# GBE2_PHY.net
KiCad netlist of a schematic drawn in Altium Designer
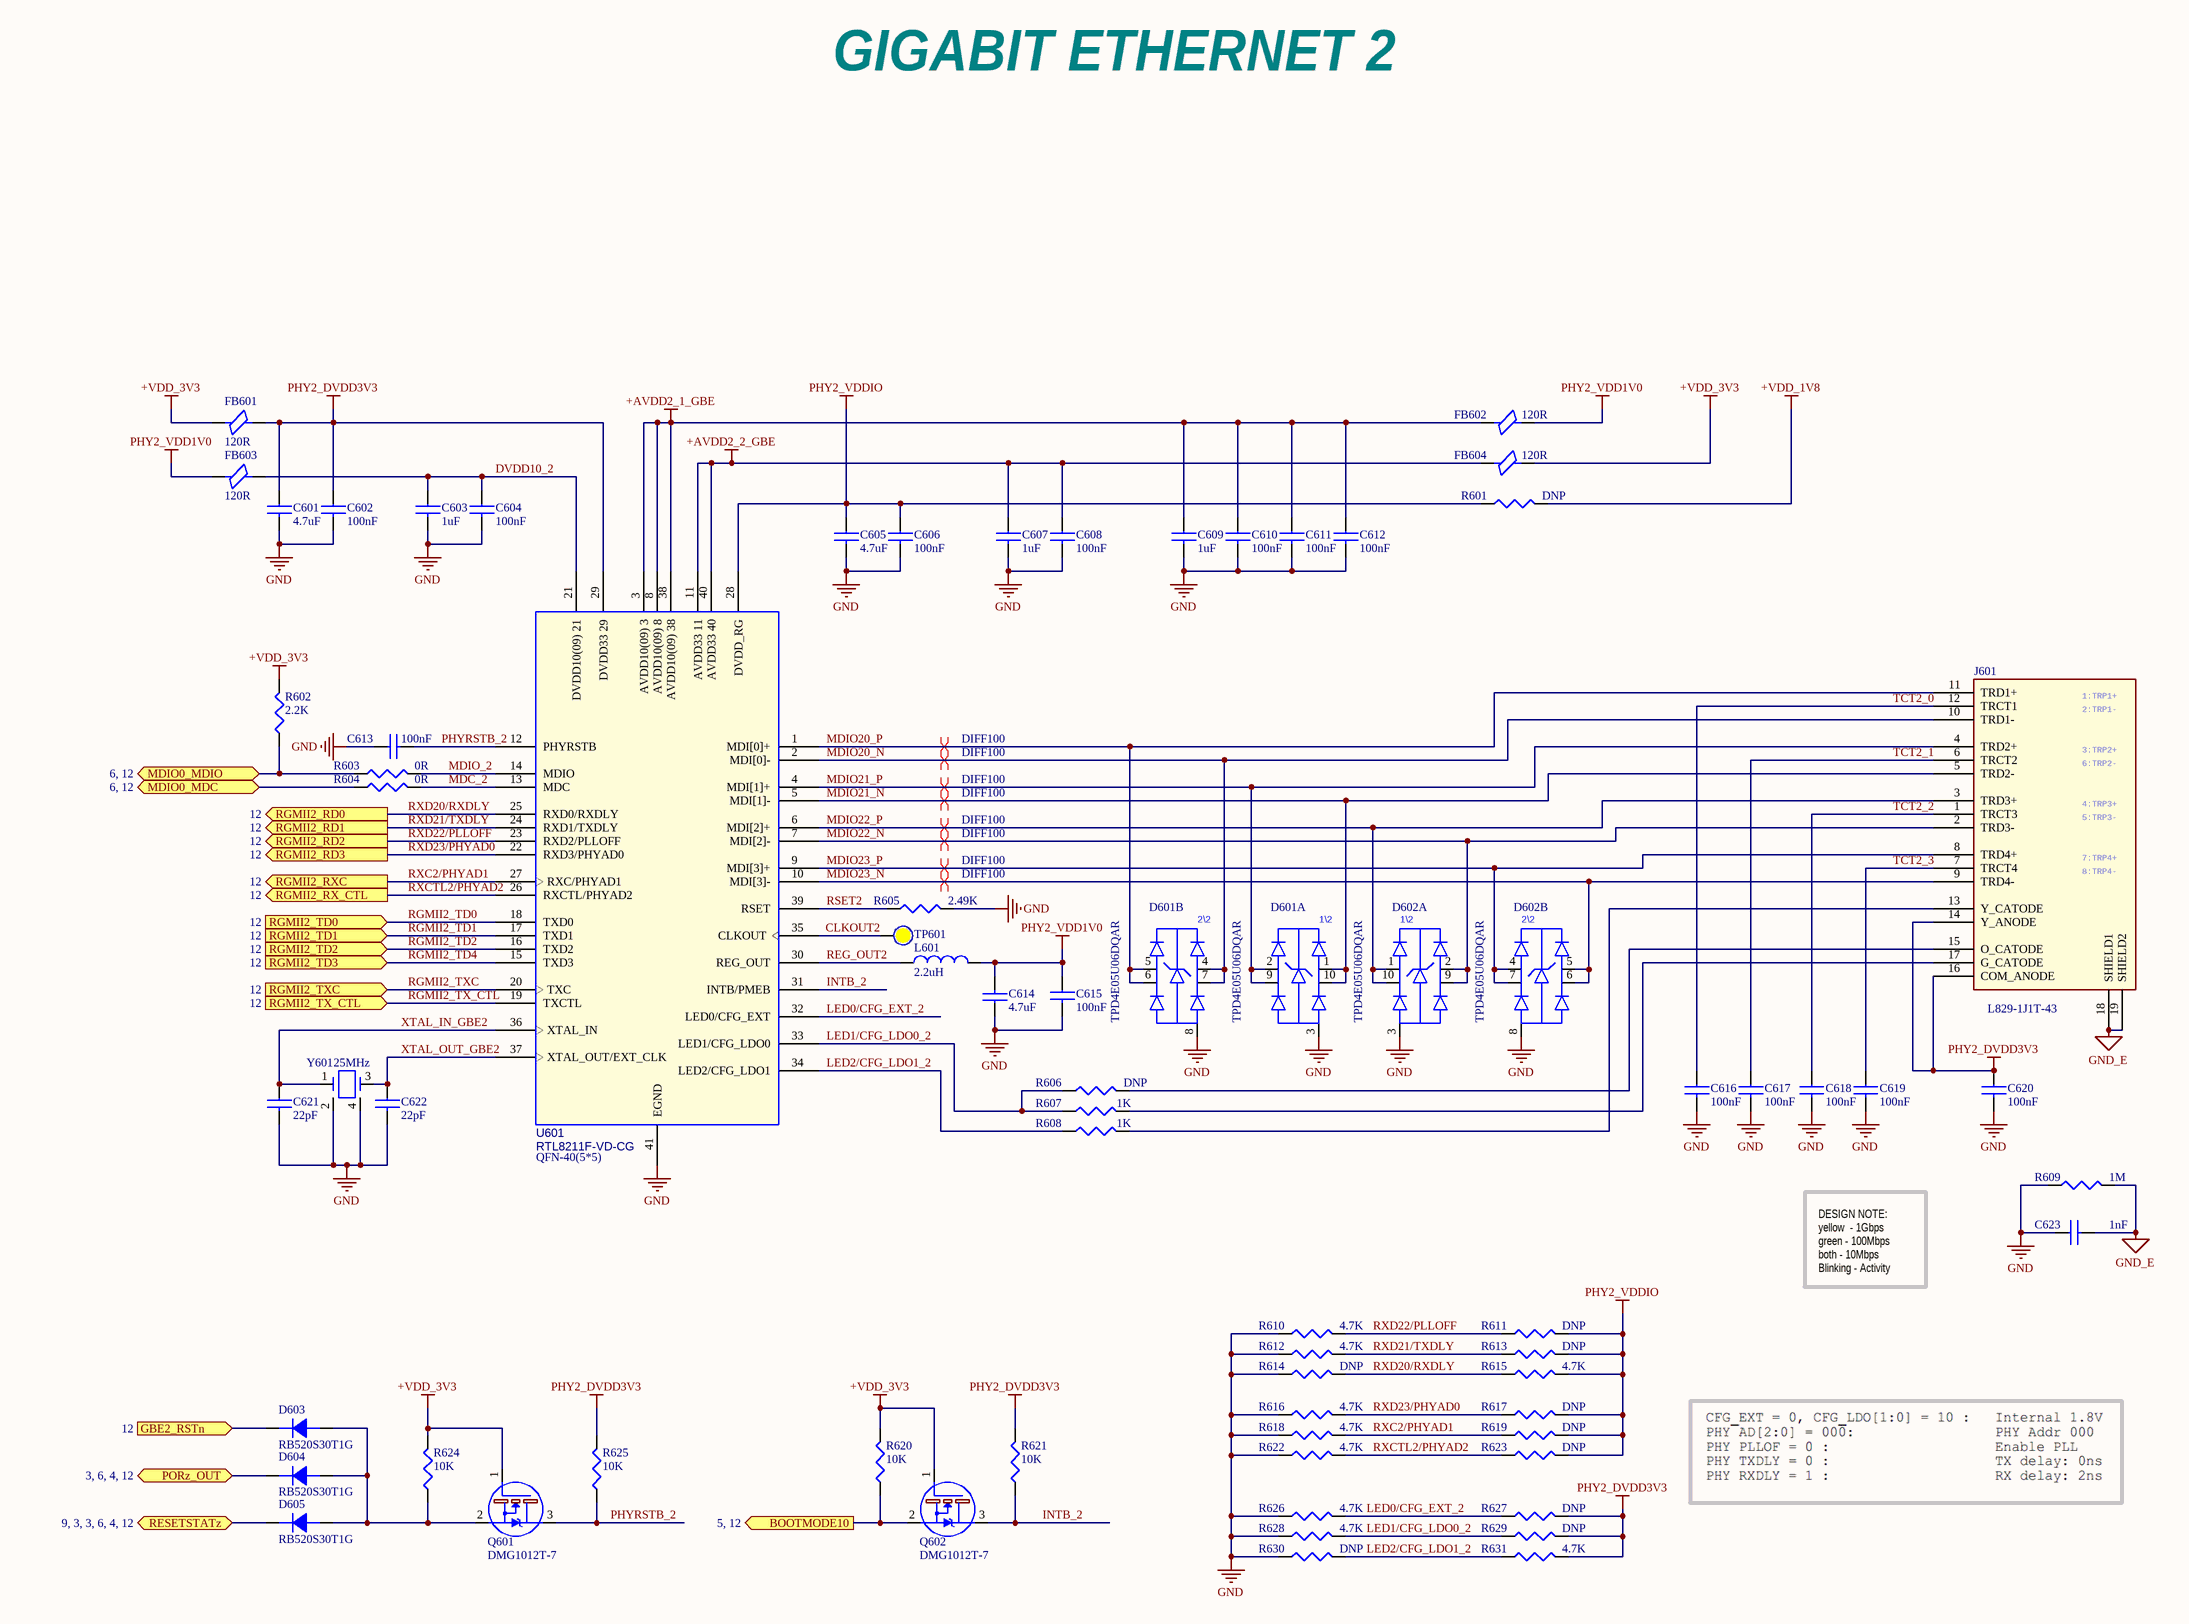
[diagram p0: GBE2 PHY.SchDoc]

(export (version "E")
  (design (tool "Eeschema 10.0.6"))
  (components
    (comp (ref "C601")
      (value "4.7uF")
      (footprint "C0402")
      (description "Multilayer Ceramic Capacitor, 4.7 uF, 6.3V, ± 10%, X5R, 0402 [1005 Metric]")
      (fields
        (field (name "MANUFACTURER") "Yageo")
        (field (name "MANUFACTURER PART NUMBER") "CC0402MRX5R5BB475")
      )
      (libsource (lib "Schlib SOM AM625") (part "CC0402MRX5R5BB475"))
    )
    (comp (ref "C602")
      (value "100nF")
      (footprint "C0201")
      (description "Multilayer Ceramic Capacitor, 0.1 uF, 16 V, ± 10%, X5R, 0201 [0603 Metric]")
      (fields
        (field (name "MANUFACTURER") "Yageo")
        (field (name "MANUFACTURER PART NUMBER") "CC0201KRX5R6BB104")
      )
      (libsource (lib "Schlib SOM AM625") (part "CC0201KRX5R6BB104"))
    )
    (comp (ref "C603")
      (value "1uF")
      (footprint "C0201")
      (description "1 µF ±20% 6.3V Ceramic Capacitor X5R 0201 (0603 Metric)")
      (fields
        (field (name "MANUFACTURER") "Yageo")
        (field (name "MANUFACTURER PART NUMBER") "CC0201MRX5R5BB105")
      )
      (libsource (lib "Schlib SOM AM625") (part "CC0201MRX5R5BB105"))
    )
    (comp (ref "C604")
      (value "100nF")
      (footprint "C0201")
      (description "Multilayer Ceramic Capacitor, 0.1 uF, 16 V, ± 10%, X5R, 0201 [0603 Metric]")
      (fields
        (field (name "MANUFACTURER") "Yageo")
        (field (name "MANUFACTURER PART NUMBER") "CC0201KRX5R6BB104")
      )
      (libsource (lib "Schlib SOM AM625") (part "CC0201KRX5R6BB104"))
    )
    (comp (ref "C605")
      (value "4.7uF")
      (footprint "C0402")
      (description "Multilayer Ceramic Capacitor, 4.7 uF, 6.3V, ± 10%, X5R, 0402 [1005 Metric]")
      (fields
        (field (name "MANUFACTURER") "Yageo")
        (field (name "MANUFACTURER PART NUMBER") "CC0402MRX5R5BB475")
      )
      (libsource (lib "Schlib SOM AM625") (part "CC0402MRX5R5BB475"))
    )
    (comp (ref "C606")
      (value "100nF")
      (footprint "C0201")
      (description "Multilayer Ceramic Capacitor, 0.1 uF, 16 V, ± 10%, X5R, 0201 [0603 Metric]")
      (fields
        (field (name "MANUFACTURER") "Yageo")
        (field (name "MANUFACTURER PART NUMBER") "CC0201KRX5R6BB104")
      )
      (libsource (lib "Schlib SOM AM625") (part "CC0201KRX5R6BB104"))
    )
    (comp (ref "C607")
      (value "1uF")
      (footprint "C0201")
      (description "1 µF ±20% 6.3V Ceramic Capacitor X5R 0201 (0603 Metric)")
      (fields
        (field (name "MANUFACTURER") "Yageo")
        (field (name "MANUFACTURER PART NUMBER") "CC0201MRX5R5BB105")
      )
      (libsource (lib "Schlib SOM AM625") (part "CC0201MRX5R5BB105"))
    )
    (comp (ref "C608")
      (value "100nF")
      (footprint "C0201")
      (description "Multilayer Ceramic Capacitor, 0.1 uF, 16 V, ± 10%, X5R, 0201 [0603 Metric]")
      (fields
        (field (name "MANUFACTURER") "Yageo")
        (field (name "MANUFACTURER PART NUMBER") "CC0201KRX5R6BB104")
      )
      (libsource (lib "Schlib SOM AM625") (part "CC0201KRX5R6BB104"))
    )
    (comp (ref "C609")
      (value "1uF")
      (footprint "C0201")
      (description "1 µF ±20% 6.3V Ceramic Capacitor X5R 0201 (0603 Metric)")
      (fields
        (field (name "MANUFACTURER") "Yageo")
        (field (name "MANUFACTURER PART NUMBER") "CC0201MRX5R5BB105")
      )
      (libsource (lib "Schlib SOM AM625") (part "CC0201MRX5R5BB105"))
    )
    (comp (ref "C610")
      (value "100nF")
      (footprint "C0201")
      (description "Multilayer Ceramic Capacitor, 0.1 uF, 16 V, ± 10%, X5R, 0201 [0603 Metric]")
      (fields
        (field (name "MANUFACTURER") "Yageo")
        (field (name "MANUFACTURER PART NUMBER") "CC0201KRX5R6BB104")
      )
      (libsource (lib "Schlib SOM AM625") (part "CC0201KRX5R6BB104"))
    )
    (comp (ref "C611")
      (value "100nF")
      (footprint "C0201")
      (description "Multilayer Ceramic Capacitor, 0.1 uF, 16 V, ± 10%, X5R, 0201 [0603 Metric]")
      (fields
        (field (name "MANUFACTURER") "Yageo")
        (field (name "MANUFACTURER PART NUMBER") "CC0201KRX5R6BB104")
      )
      (libsource (lib "Schlib SOM AM625") (part "CC0201KRX5R6BB104"))
    )
    (comp (ref "C612")
      (value "100nF")
      (footprint "C0201")
      (description "Multilayer Ceramic Capacitor, 0.1 uF, 16 V, ± 10%, X5R, 0201 [0603 Metric]")
      (fields
        (field (name "MANUFACTURER") "Yageo")
        (field (name "MANUFACTURER PART NUMBER") "CC0201KRX5R6BB104")
      )
      (libsource (lib "Schlib SOM AM625") (part "CC0201KRX5R6BB104"))
    )
    (comp (ref "C613")
      (value "100nF")
      (footprint "C0201")
      (description "Multilayer Ceramic Capacitor, 0.1 uF, 16 V, ± 10%, X5R, 0201 [0603 Metric]")
      (fields
        (field (name "MANUFACTURER") "Yageo")
        (field (name "MANUFACTURER PART NUMBER") "CC0201KRX5R6BB104")
      )
      (libsource (lib "Schlib SOM AM625") (part "CC0201KRX5R6BB104"))
    )
    (comp (ref "C614")
      (value "4.7uF")
      (footprint "C0402")
      (description "Multilayer Ceramic Capacitor, 4.7 uF, 6.3V, ± 10%, X5R, 0402 [1005 Metric]")
      (fields
        (field (name "MANUFACTURER") "Yageo")
        (field (name "MANUFACTURER PART NUMBER") "CC0402MRX5R5BB475")
      )
      (libsource (lib "Schlib SOM AM625") (part "CC0402MRX5R5BB475"))
    )
    (comp (ref "C615")
      (value "100nF")
      (footprint "C0201")
      (description "Multilayer Ceramic Capacitor, 0.1 uF, 16 V, ± 10%, X5R, 0201 [0603 Metric]")
      (fields
        (field (name "MANUFACTURER") "Yageo")
        (field (name "MANUFACTURER PART NUMBER") "CC0201KRX5R6BB104")
      )
      (libsource (lib "Schlib SOM AM625") (part "CC0201KRX5R6BB104"))
    )
    (comp (ref "C616")
      (value "100nF")
      (footprint "C0402")
      (description "Multilayer Ceramic Capacitor, 0.1 uF, 50 V, ± 10%, X5R, 0402 [1005 Metric]")
      (fields
        (field (name "MANUFACTURER") "TDK")
        (field (name "MANUFACTURER PART NUMBER") "C1005X5R1H104K050BB")
      )
      (libsource (lib "Schlib SOM AM625") (part "C1005X5R1H104K050BB"))
    )
    (comp (ref "C617")
      (value "100nF")
      (footprint "C0402")
      (description "Multilayer Ceramic Capacitor, 0.1 uF, 50 V, ± 10%, X5R, 0402 [1005 Metric]")
      (fields
        (field (name "MANUFACTURER") "TDK")
        (field (name "MANUFACTURER PART NUMBER") "C1005X5R1H104K050BB")
      )
      (libsource (lib "Schlib SOM AM625") (part "C1005X5R1H104K050BB"))
    )
    (comp (ref "C618")
      (value "100nF")
      (footprint "C0402")
      (description "Multilayer Ceramic Capacitor, 0.1 uF, 50 V, ± 10%, X5R, 0402 [1005 Metric]")
      (fields
        (field (name "MANUFACTURER") "TDK")
        (field (name "MANUFACTURER PART NUMBER") "C1005X5R1H104K050BB")
      )
      (libsource (lib "Schlib SOM AM625") (part "C1005X5R1H104K050BB"))
    )
    (comp (ref "C619")
      (value "100nF")
      (footprint "C0402")
      (description "Multilayer Ceramic Capacitor, 0.1 uF, 50 V, ± 10%, X5R, 0402 [1005 Metric]")
      (fields
        (field (name "MANUFACTURER") "TDK")
        (field (name "MANUFACTURER PART NUMBER") "C1005X5R1H104K050BB")
      )
      (libsource (lib "Schlib SOM AM625") (part "C1005X5R1H104K050BB"))
    )
    (comp (ref "C620")
      (value "100nF")
      (footprint "C0402")
      (description "Multilayer Ceramic Capacitor, 0.1 uF, 50 V, ± 10%, X5R, 0402 [1005 Metric]")
      (fields
        (field (name "MANUFACTURER") "TDK")
        (field (name "MANUFACTURER PART NUMBER") "C1005X5R1H104K050BB")
      )
      (libsource (lib "Schlib SOM AM625") (part "C1005X5R1H104K050BB"))
    )
    (comp (ref "C621")
      (value "22pF")
      (footprint "C0201")
      (description "0201 22 pF 50 V ±5 % Tolerance NP0 SMT Multilayer Ceramic Capacitor")
      (fields
        (field (name "MANUFACTURER") "Yageo")
        (field (name "MANUFACTURER PART NUMBER") "CC0201JRNPO9BN220")
      )
      (libsource (lib "Schlib SOM AM625") (part "CC0201JRNPO9BN220"))
    )
    (comp (ref "C622")
      (value "22pF")
      (footprint "C0201")
      (description "0201 22 pF 50 V ±5 % Tolerance NP0 SMT Multilayer Ceramic Capacitor")
      (fields
        (field (name "MANUFACTURER") "Yageo")
        (field (name "MANUFACTURER PART NUMBER") "CC0201JRNPO9BN220")
      )
      (libsource (lib "Schlib SOM AM625") (part "CC0201JRNPO9BN220"))
    )
    (comp (ref "C623")
      (value "1nF")
      (footprint "C1206B/3216MM")
      (description "Cap Ceramic 0.001uF 1000V X7R 10% Pad SMD 1206 125°C Low ESR Automotive Medical T/R")
      (fields
        (field (name "MANUFACTURER") "KEMET")
        (field (name "MANUFACTURER PART NUMBER") "C1206C102KDRACAUTO")
      )
      (libsource (lib "Schlib SOM AM625") (part "C1206C102KDRACAUTO"))
    )
    (comp (ref "D601")
      (value "TPD4E05U06DQAR")
      (footprint "10-USON")
      (description "Quad 0.5-pF, 5.5-V, ±12-kV ESD protection diode for USB, HDMI & High Speed Interfaces")
      (fields (field (name "MANUFACTURER") "Texas Instruments"))
      (libsource (lib "Schlib SOM AM625") (part "TPD4E05U06DQAR"))
    )
    (comp (ref "D602")
      (value "TPD4E05U06DQAR")
      (footprint "10-USON")
      (description "Quad 0.5-pF, 5.5-V, ±12-kV ESD protection diode for USB, HDMI & High Speed Interfaces")
      (fields (field (name "MANUFACTURER") "Texas Instruments"))
      (libsource (lib "Schlib SOM AM625") (part "TPD4E05U06DQAR"))
    )
    (comp (ref "D603")
      (value "RB520S30T1G")
      (footprint "sod_523")
      (description "Diode Schottky 30V 0.2A 2-Pin SOD-523 T/R - Product that comes on tape, but is not reeled")
      (fields (field (name "MANUFACTURER") "ON Semiconductor"))
      (libsource (lib "Schlib SOM AM625") (part "RB520S30T1G"))
    )
    (comp (ref "D604")
      (value "RB520S30T1G")
      (footprint "sod_523")
      (description "Diode Schottky 30V 0.2A 2-Pin SOD-523 T/R - Product that comes on tape, but is not reeled")
      (fields (field (name "MANUFACTURER") "ON Semiconductor"))
      (libsource (lib "Schlib SOM AM625") (part "RB520S30T1G"))
    )
    (comp (ref "D605")
      (value "RB520S30T1G")
      (footprint "sod_523")
      (description "Diode Schottky 30V 0.2A 2-Pin SOD-523 T/R - Product that comes on tape, but is not reeled")
      (fields (field (name "MANUFACTURER") "ON Semiconductor"))
      (libsource (lib "Schlib SOM AM625") (part "RB520S30T1G"))
    )
    (comp (ref "FB601")
      (value "120R")
      (footprint "FB0402")
      (description "Ferrite Beads Multi-Layer 120Ohm 25% 100MHz 1.3A 0.09Ohm DCR 0402 Automotive T/R")
      (fields
        (field (name "MANUFACTURER") "Murata")
        (field (name "MANUFACTURER PART NUMBER") "BLM15PD121SZ1D")
      )
      (libsource (lib "Schlib SOM AM625") (part "BLM15PD121SZ1D"))
    )
    (comp (ref "FB602")
      (value "120R")
      (footprint "FB0402")
      (description "Ferrite Beads Multi-Layer 120Ohm 25% 100MHz 1.3A 0.09Ohm DCR 0402 Automotive T/R")
      (fields
        (field (name "MANUFACTURER") "Murata")
        (field (name "MANUFACTURER PART NUMBER") "BLM15PD121SZ1D")
      )
      (libsource (lib "Schlib SOM AM625") (part "BLM15PD121SZ1D"))
    )
    (comp (ref "FB603")
      (value "120R")
      (footprint "FB0402")
      (description "Ferrite Beads Multi-Layer 120Ohm 25% 100MHz 1.3A 0.09Ohm DCR 0402 Automotive T/R")
      (fields
        (field (name "MANUFACTURER") "Murata")
        (field (name "MANUFACTURER PART NUMBER") "BLM15PD121SZ1D")
      )
      (libsource (lib "Schlib SOM AM625") (part "BLM15PD121SZ1D"))
    )
    (comp (ref "FB604")
      (value "120R")
      (footprint "FB0402")
      (description "Ferrite Beads Multi-Layer 120Ohm 25% 100MHz 1.3A 0.09Ohm DCR 0402 Automotive T/R")
      (fields
        (field (name "MANUFACTURER") "Murata")
        (field (name "MANUFACTURER PART NUMBER") "BLM15PD121SZ1D")
      )
      (libsource (lib "Schlib SOM AM625") (part "BLM15PD121SZ1D"))
    )
    (comp (ref "J601")
      (value "L829-1J1T-43")
      (footprint "L829-1J1T-43")
      (description "CONN MAGJACK 1PORT SHLD 1000BT")
      (fields
        (field (name "MANUFACTURER") "Bel Fuse Inc")
        (field (name ".CHECKED PCB") "RF")
        (field (name ".CHECKED SCH") "RF")
      )
      (libsource (lib "Schlib SOM AM625") (part "L829-1J1T-43"))
    )
    (comp (ref "L601")
      (value "2.2uH")
      (footprint "l2016")
      (description "Inductor Power Shielded Wirewound 2.2uH 20% 1MHz Metal 1.4A 0.168Ohm DCR 0806 T/R")
      (fields
        (field (name "MANUFACTURER") "Murata")
        (field (name "MANUFACTURER PART NUMBER") "DFE201610P-2R2M=P2")
      )
      (libsource (lib "Schlib SOM AM625") (part "DFE201610P-2R2M=P2"))
    )
    (comp (ref "Q601")
      (value "DMG1012T-7")
      (footprint "sot_523")
      (description "Transistor MOSFET NTR4003NT1G, SOT23, ON Semi")
      (fields (field (name "MANUFACTURER") "Diodes"))
      (libsource (lib "Schlib SOM AM625") (part "DMG1012T-7"))
    )
    (comp (ref "Q602")
      (value "DMG1012T-7")
      (footprint "sot_523")
      (description "Transistor MOSFET NTR4003NT1G, SOT23, ON Semi")
      (fields (field (name "MANUFACTURER") "Diodes"))
      (libsource (lib "Schlib SOM AM625") (part "DMG1012T-7"))
    )
    (comp (ref "R601")
      (value "DNP")
      (footprint "R0402")
      (description "Zero Ohm Resistor, Jumper, 0402 [1005 Metric], Thick Film, 63 mW, 1 A, Surface Mount")
      (fields
        (field (name "MANUFACTURER") "Yageo")
        (field (name "MANUFACTURER PART NUMBER") "RC0402JR-070RL")
      )
      (libsource (lib "Schlib SOM AM625") (part "RC0402JR-070RL"))
    )
    (comp (ref "R602")
      (value "2.2K")
      (footprint "R0201")
      (description "SMD Chip Resistor, 2.2 kOhm, ± 1%, 50 mW, 0201 [0603 Metric], Thick Film, General Purpose")
      (fields
        (field (name "MANUFACTURER") "Yageo")
        (field (name "MANUFACTURER PART NUMBER") "RC0201FR-072K2L")
      )
      (libsource (lib "Schlib SOM AM625") (part "RC0201FR-072K2L"))
    )
    (comp (ref "R603")
      (value "0R")
      (footprint "R0201")
      (description "Zero Ohm Resistor, Jumper, 0201 [0603 Metric], Thick Film, 50 mW, 500 mA, Surface Mount")
      (fields
        (field (name "MANUFACTURER") "Yageo")
        (field (name "MANUFACTURER PART NUMBER") "RC0201JR-070RL")
      )
      (libsource (lib "Schlib SOM AM625") (part "RC0201JR-070RL"))
    )
    (comp (ref "R604")
      (value "0R")
      (footprint "R0201")
      (description "Zero Ohm Resistor, Jumper, 0201 [0603 Metric], Thick Film, 50 mW, 500 mA, Surface Mount")
      (fields
        (field (name "MANUFACTURER") "Yageo")
        (field (name "MANUFACTURER PART NUMBER") "RC0201JR-070RL")
      )
      (libsource (lib "Schlib SOM AM625") (part "RC0201JR-070RL"))
    )
    (comp (ref "R605")
      (value "2.49K")
      (footprint "R0201")
      (description "SMD Chip Resistor, 2.49 kOhm, ± 1%, 50 mW, 0201 [0603 Metric], Thick Film, General Purpose")
      (fields
        (field (name "MANUFACTURER") "Yageo")
        (field (name "MANUFACTURER PART NUMBER") "RC0201FR-072K49L")
      )
      (libsource (lib "Schlib SOM AM625") (part "RC0201FR-072K49L"))
    )
    (comp (ref "R606")
      (value "DNP")
      (footprint "R0402")
      (description "Zero Ohm Resistor, Jumper, 0402 [1005 Metric], Thick Film, 63 mW, 1 A, Surface Mount")
      (fields
        (field (name "MANUFACTURER") "Yageo")
        (field (name "MANUFACTURER PART NUMBER") "RC0402JR-070RL")
      )
      (libsource (lib "Schlib SOM AM625") (part "RC0402JR-070RL"))
    )
    (comp (ref "R607")
      (value "1K")
      (footprint "R0402")
      (description "SMD Chip Resistor, 1 kOhm, ± 1%, 63 mW, 0402 [1005 Metric], Thick Film, General Purpose")
      (fields
        (field (name "MANUFACTURER") "Yageo")
        (field (name "MANUFACTURER PART NUMBER") "RC0402FR-071KL")
      )
      (libsource (lib "Schlib SOM AM625") (part "RC0402FR-071KL"))
    )
    (comp (ref "R608")
      (value "1K")
      (footprint "R0402")
      (description "SMD Chip Resistor, 1 kOhm, ± 1%, 63 mW, 0402 [1005 Metric], Thick Film, General Purpose")
      (fields
        (field (name "MANUFACTURER") "Yageo")
        (field (name "MANUFACTURER PART NUMBER") "RC0402FR-071KL")
      )
      (libsource (lib "Schlib SOM AM625") (part "RC0402FR-071KL"))
    )
    (comp (ref "R609")
      (value "1M")
      (footprint "R1206B/3216MM")
      (description "SMD Chip Resistor, 1 MOhm, ± 1%, 250 mW, 1206 [3216 Metric], Thick Film, General Purpose")
      (fields
        (field (name "MANUFACTURER") "Yageo")
        (field (name "MANUFACTURER PART NUMBER") "RC1206FR-071ML")
      )
      (libsource (lib "Schlib SOM AM625") (part "RC1206FR-071ML"))
    )
    (comp (ref "R610")
      (value "4.7K")
      (footprint "R0201")
      (description "SMD Chip Resistor, 4.7 kOhm, ± 5%, 50 mW, 0201 [0603 Metric], Thick Film, General Purpose")
      (fields
        (field (name "MANUFACTURER") "Yageo")
        (field (name "MANUFACTURER PART NUMBER") "RC0201JR-074K7L")
      )
      (libsource (lib "Schlib SOM AM625") (part "RC0201JR-074K7L"))
    )
    (comp (ref "R611")
      (value "DNP")
      (footprint "R0201")
      (description "SMD Chip Resistor, 4.7 kOhm, ± 5%, 50 mW, 0201 [0603 Metric], Thick Film, General Purpose")
      (fields
        (field (name "MANUFACTURER") "Yageo")
        (field (name "MANUFACTURER PART NUMBER") "RC0201JR-074K7L")
      )
      (libsource (lib "Schlib SOM AM625") (part "RC0201JR-074K7L"))
    )
    (comp (ref "R612")
      (value "4.7K")
      (footprint "R0201")
      (description "SMD Chip Resistor, 4.7 kOhm, ± 5%, 50 mW, 0201 [0603 Metric], Thick Film, General Purpose")
      (fields
        (field (name "MANUFACTURER") "Yageo")
        (field (name "MANUFACTURER PART NUMBER") "RC0201JR-074K7L")
      )
      (libsource (lib "Schlib SOM AM625") (part "RC0201JR-074K7L"))
    )
    (comp (ref "R613")
      (value "DNP")
      (footprint "R0201")
      (description "SMD Chip Resistor, 4.7 kOhm, ± 5%, 50 mW, 0201 [0603 Metric], Thick Film, General Purpose")
      (fields
        (field (name "MANUFACTURER") "Yageo")
        (field (name "MANUFACTURER PART NUMBER") "RC0201JR-074K7L")
      )
      (libsource (lib "Schlib SOM AM625") (part "RC0201JR-074K7L"))
    )
    (comp (ref "R614")
      (value "DNP")
      (footprint "R0201")
      (description "SMD Chip Resistor, 4.7 kOhm, ± 5%, 50 mW, 0201 [0603 Metric], Thick Film, General Purpose")
      (fields
        (field (name "MANUFACTURER") "Yageo")
        (field (name "MANUFACTURER PART NUMBER") "RC0201JR-074K7L")
      )
      (libsource (lib "Schlib SOM AM625") (part "RC0201JR-074K7L"))
    )
    (comp (ref "R615")
      (value "4.7K")
      (footprint "R0201")
      (description "SMD Chip Resistor, 4.7 kOhm, ± 5%, 50 mW, 0201 [0603 Metric], Thick Film, General Purpose")
      (fields
        (field (name "MANUFACTURER") "Yageo")
        (field (name "MANUFACTURER PART NUMBER") "RC0201JR-074K7L")
      )
      (libsource (lib "Schlib SOM AM625") (part "RC0201JR-074K7L"))
    )
    (comp (ref "R616")
      (value "4.7K")
      (footprint "R0201")
      (description "SMD Chip Resistor, 4.7 kOhm, ± 5%, 50 mW, 0201 [0603 Metric], Thick Film, General Purpose")
      (fields
        (field (name "MANUFACTURER") "Yageo")
        (field (name "MANUFACTURER PART NUMBER") "RC0201JR-074K7L")
      )
      (libsource (lib "Schlib SOM AM625") (part "RC0201JR-074K7L"))
    )
    (comp (ref "R617")
      (value "DNP")
      (footprint "R0201")
      (description "SMD Chip Resistor, 4.7 kOhm, ± 5%, 50 mW, 0201 [0603 Metric], Thick Film, General Purpose")
      (fields
        (field (name "MANUFACTURER") "Yageo")
        (field (name "MANUFACTURER PART NUMBER") "RC0201JR-074K7L")
      )
      (libsource (lib "Schlib SOM AM625") (part "RC0201JR-074K7L"))
    )
    (comp (ref "R618")
      (value "4.7K")
      (footprint "R0201")
      (description "SMD Chip Resistor, 4.7 kOhm, ± 5%, 50 mW, 0201 [0603 Metric], Thick Film, General Purpose")
      (fields
        (field (name "MANUFACTURER") "Yageo")
        (field (name "MANUFACTURER PART NUMBER") "RC0201JR-074K7L")
      )
      (libsource (lib "Schlib SOM AM625") (part "RC0201JR-074K7L"))
    )
    (comp (ref "R619")
      (value "DNP")
      (footprint "R0201")
      (description "SMD Chip Resistor, 4.7 kOhm, ± 5%, 50 mW, 0201 [0603 Metric], Thick Film, General Purpose")
      (fields
        (field (name "MANUFACTURER") "Yageo")
        (field (name "MANUFACTURER PART NUMBER") "RC0201JR-074K7L")
      )
      (libsource (lib "Schlib SOM AM625") (part "RC0201JR-074K7L"))
    )
    (comp (ref "R620")
      (value "10K")
      (footprint "R0201")
      (description "SMD Chip Resistor, 10 kOhm, ± 1%, 50 mW, 0201 [0603 Metric], Thick Film, General Purpose")
      (fields
        (field (name "MANUFACTURER") "Yageo")
        (field (name "MANUFACTURER PART NUMBER") "RC0201FR-0710KL")
      )
      (libsource (lib "Schlib SOM AM625") (part "RC0201FR-0710KL"))
    )
    (comp (ref "R621")
      (value "10K")
      (footprint "R0201")
      (description "SMD Chip Resistor, 10 kOhm, ± 1%, 50 mW, 0201 [0603 Metric], Thick Film, General Purpose")
      (fields
        (field (name "MANUFACTURER") "Yageo")
        (field (name "MANUFACTURER PART NUMBER") "RC0201FR-0710KL")
      )
      (libsource (lib "Schlib SOM AM625") (part "RC0201FR-0710KL"))
    )
    (comp (ref "R622")
      (value "4.7K")
      (footprint "R0201")
      (description "SMD Chip Resistor, 4.7 kOhm, ± 5%, 50 mW, 0201 [0603 Metric], Thick Film, General Purpose")
      (fields
        (field (name "MANUFACTURER") "Yageo")
        (field (name "MANUFACTURER PART NUMBER") "RC0201JR-074K7L")
      )
      (libsource (lib "Schlib SOM AM625") (part "RC0201JR-074K7L"))
    )
    (comp (ref "R623")
      (value "DNP")
      (footprint "R0201")
      (description "SMD Chip Resistor, 4.7 kOhm, ± 5%, 50 mW, 0201 [0603 Metric], Thick Film, General Purpose")
      (fields
        (field (name "MANUFACTURER") "Yageo")
        (field (name "MANUFACTURER PART NUMBER") "RC0201JR-074K7L")
      )
      (libsource (lib "Schlib SOM AM625") (part "RC0201JR-074K7L"))
    )
    (comp (ref "R624")
      (value "10K")
      (footprint "R0201")
      (description "SMD Chip Resistor, 10 kOhm, ± 1%, 50 mW, 0201 [0603 Metric], Thick Film, General Purpose")
      (fields
        (field (name "MANUFACTURER") "Yageo")
        (field (name "MANUFACTURER PART NUMBER") "RC0201FR-0710KL")
      )
      (libsource (lib "Schlib SOM AM625") (part "RC0201FR-0710KL"))
    )
    (comp (ref "R625")
      (value "10K")
      (footprint "R0201")
      (description "SMD Chip Resistor, 10 kOhm, ± 1%, 50 mW, 0201 [0603 Metric], Thick Film, General Purpose")
      (fields
        (field (name "MANUFACTURER") "Yageo")
        (field (name "MANUFACTURER PART NUMBER") "RC0201FR-0710KL")
      )
      (libsource (lib "Schlib SOM AM625") (part "RC0201FR-0710KL"))
    )
    (comp (ref "R626")
      (value "4.7K")
      (footprint "R0201")
      (description "SMD Chip Resistor, 4.7 kOhm, ± 5%, 50 mW, 0201 [0603 Metric], Thick Film, General Purpose")
      (fields
        (field (name "MANUFACTURER") "Yageo")
        (field (name "MANUFACTURER PART NUMBER") "RC0201JR-074K7L")
      )
      (libsource (lib "Schlib SOM AM625") (part "RC0201JR-074K7L"))
    )
    (comp (ref "R627")
      (value "DNP")
      (footprint "R0201")
      (description "SMD Chip Resistor, 4.7 kOhm, ± 5%, 50 mW, 0201 [0603 Metric], Thick Film, General Purpose")
      (fields
        (field (name "MANUFACTURER") "Yageo")
        (field (name "MANUFACTURER PART NUMBER") "RC0201JR-074K7L")
      )
      (libsource (lib "Schlib SOM AM625") (part "RC0201JR-074K7L"))
    )
    (comp (ref "R628")
      (value "4.7K")
      (footprint "R0201")
      (description "SMD Chip Resistor, 4.7 kOhm, ± 5%, 50 mW, 0201 [0603 Metric], Thick Film, General Purpose")
      (fields
        (field (name "MANUFACTURER") "Yageo")
        (field (name "MANUFACTURER PART NUMBER") "RC0201JR-074K7L")
      )
      (libsource (lib "Schlib SOM AM625") (part "RC0201JR-074K7L"))
    )
    (comp (ref "R629")
      (value "DNP")
      (footprint "R0201")
      (description "SMD Chip Resistor, 4.7 kOhm, ± 5%, 50 mW, 0201 [0603 Metric], Thick Film, General Purpose")
      (fields
        (field (name "MANUFACTURER") "Yageo")
        (field (name "MANUFACTURER PART NUMBER") "RC0201JR-074K7L")
      )
      (libsource (lib "Schlib SOM AM625") (part "RC0201JR-074K7L"))
    )
    (comp (ref "R630")
      (value "DNP")
      (footprint "R0201")
      (description "SMD Chip Resistor, 4.7 kOhm, ± 5%, 50 mW, 0201 [0603 Metric], Thick Film, General Purpose")
      (fields
        (field (name "MANUFACTURER") "Yageo")
        (field (name "MANUFACTURER PART NUMBER") "RC0201JR-074K7L")
      )
      (libsource (lib "Schlib SOM AM625") (part "RC0201JR-074K7L"))
    )
    (comp (ref "R631")
      (value "4.7K")
      (footprint "R0201")
      (description "SMD Chip Resistor, 4.7 kOhm, ± 5%, 50 mW, 0201 [0603 Metric], Thick Film, General Purpose")
      (fields
        (field (name "MANUFACTURER") "Yageo")
        (field (name "MANUFACTURER PART NUMBER") "RC0201JR-074K7L")
      )
      (libsource (lib "Schlib SOM AM625") (part "RC0201JR-074K7L"))
    )
    (comp (ref "TP601")
      (value "~")
      (footprint "Test Point 1 MM")
      (description "Test Point")
      (libsource (lib "BYTECH_HW_LIB_2019") (part "Test Point"))
    )
    (comp (ref "U601")
      (value "RTL8211F-VD-CG")
      (footprint "qfn40_0D4_5x5mm")
      (description "IC, Interface, Ethernet, RTL8211F-VD-CG, QFN-40(5*5)")
      (fields
        (field (name "MANUFACTURER") "Realtek")
        (field (name "PACKAGE SIZE") "QFN-40(5*5)")
        (field (name "Comment") "RTL8211")
      )
      (libsource (lib "Schlib SOM AM625") (part "RTL8211"))
    )
    (comp (ref "Y601")
      (value "25MHz")
      (footprint "x4-smd-3_2x2_5x1_0mm")
      (description "Crystal, 25MHZ, 18PF, SMD")
      (fields (field (name "MANUFACTURER") "IQD") (field (name "MANUFACTURER PART NUMBER") "LFXTAL055299"))
      (libsource (lib "Schlib SOM AM625") (part "LFXTAL055299"))
    )
  )
  (nets
    (net (code "1") (name "+AVDD2_1_GBE") (class "Default")
      (node (ref "C609") (pin "1") (pinfunction "1_1") (pintype "passive"))
      (node (ref "C610") (pin "1") (pinfunction "1_1") (pintype "passive"))
      (node (ref "C611") (pin "1") (pinfunction "1_1") (pintype "passive"))
      (node (ref "C612") (pin "1") (pinfunction "1_1") (pintype "passive"))
      (node (ref "FB602") (pin "1") (pinfunction "1_1") (pintype "passive"))
      (node (ref "U601") (pin "3") (pinfunction "AVDD10(09)_3_3") (pintype "power_in"))
      (node (ref "U601") (pin "38") (pinfunction "AVDD10(09)_38_38") (pintype "power_in"))
      (node (ref "U601") (pin "8") (pinfunction "AVDD10(09)_8_8") (pintype "power_in"))
    )
    (net (code "2") (name "+AVDD2_2_GBE") (class "Default")
      (node (ref "C607") (pin "1") (pinfunction "1_1") (pintype "passive"))
      (node (ref "C608") (pin "1") (pinfunction "1_1") (pintype "passive"))
      (node (ref "FB604") (pin "1") (pinfunction "1_1") (pintype "passive"))
      (node (ref "U601") (pin "11") (pinfunction "AVDD33_11_11") (pintype "power_in"))
      (node (ref "U601") (pin "40") (pinfunction "AVDD33_40_40") (pintype "power_in"))
    )
    (net (code "3") (name "+VDD_1V8") (class "Default")
      (node (ref "R601") (pin "2") (pinfunction "2_2") (pintype "passive"))
    )
    (net (code "4") (name "+VDD_3V3") (class "Default")
      (node (ref "FB601") (pin "1") (pinfunction "1_1") (pintype "passive"))
      (node (ref "FB604") (pin "2") (pinfunction "2_2") (pintype "passive"))
      (node (ref "Q601") (pin "1") (pinfunction "G_1") (pintype "passive"))
      (node (ref "Q602") (pin "1") (pinfunction "G_1") (pintype "passive"))
      (node (ref "R602") (pin "2") (pinfunction "2_2") (pintype "passive"))
      (node (ref "R620") (pin "2") (pinfunction "2_2") (pintype "passive"))
      (node (ref "R624") (pin "2") (pinfunction "2_2") (pintype "passive"))
    )
    (net (code "5") (name "/BOOTMODE10") (class "Default")
      (node (ref "Q602") (pin "2") (pinfunction "S_2") (pintype "passive"))
      (node (ref "R620") (pin "1") (pinfunction "1_1") (pintype "passive"))
    )
    (net (code "6") (name "/CLKOUT2") (class "Default")
      (node (ref "TP601") (pin "0") (pinfunction "0_0") (pintype "passive"))
      (node (ref "U601") (pin "35") (pinfunction "CLKOUT_35") (pintype "passive"))
    )
    (net (code "7") (name "/DVDD10_2") (class "Default")
      (node (ref "C603") (pin "1") (pinfunction "1_1") (pintype "passive"))
      (node (ref "C604") (pin "1") (pinfunction "1_1") (pintype "passive"))
      (node (ref "FB603") (pin "2") (pinfunction "2_2") (pintype "passive"))
      (node (ref "U601") (pin "21") (pinfunction "DVDD10(09)_21_21") (pintype "power_in"))
    )
    (net (code "8") (name "/GBE2_RSTn") (class "Default")
      (node (ref "D603") (pin "2") (pinfunction "C_2") (pintype "passive"))
    )
    (net (code "9") (name "/INTB_2") (class "Default")
      (node (ref "Q602") (pin "3") (pinfunction "D_3") (pintype "passive"))
      (node (ref "R621") (pin "1") (pinfunction "1_1") (pintype "passive"))
      (node (ref "U601") (pin "31") (pinfunction "INTB/PMEB_31") (pintype "passive"))
    )
    (net (code "10") (name "/LED0{slash}CFG_EXT_2") (class "Default")
      (node (ref "R626") (pin "2") (pinfunction "2_2") (pintype "passive"))
      (node (ref "R627") (pin "1") (pinfunction "1_1") (pintype "passive"))
      (node (ref "U601") (pin "32") (pinfunction "LED0/CFG_EXT_32") (pintype "passive"))
    )
    (net (code "11") (name "/LED1{slash}CFG_LDO0_2") (class "Default")
      (node (ref "R606") (pin "1") (pinfunction "1_1") (pintype "passive"))
      (node (ref "R607") (pin "1") (pinfunction "1_1") (pintype "passive"))
      (node (ref "R628") (pin "2") (pinfunction "2_2") (pintype "passive"))
      (node (ref "R629") (pin "1") (pinfunction "1_1") (pintype "passive"))
      (node (ref "U601") (pin "33") (pinfunction "LED1/CFG_LDO0_33") (pintype "passive"))
    )
    (net (code "12") (name "/LED2{slash}CFG_LDO1_2") (class "Default")
      (node (ref "R608") (pin "1") (pinfunction "1_1") (pintype "passive"))
      (node (ref "R630") (pin "2") (pinfunction "2_2") (pintype "passive"))
      (node (ref "R631") (pin "1") (pinfunction "1_1") (pintype "passive"))
      (node (ref "U601") (pin "34") (pinfunction "LED2/CFG_LDO1_34") (pintype "passive"))
    )
    (net (code "13") (name "/MDC_2") (class "Default")
      (node (ref "R604") (pin "2") (pinfunction "2_2") (pintype "passive"))
      (node (ref "U601") (pin "13") (pinfunction "MDC_13") (pintype "passive"))
    )
    (net (code "14") (name "/MDIO0_MDC") (class "Default")
      (node (ref "R604") (pin "1") (pinfunction "1_1") (pintype "passive"))
    )
    (net (code "15") (name "/MDIO0_MDIO") (class "Default")
      (node (ref "R602") (pin "1") (pinfunction "1_1") (pintype "passive"))
      (node (ref "R603") (pin "1") (pinfunction "1_1") (pintype "passive"))
    )
    (net (code "16") (name "/MDIO20_N") (class "Default")
      (node (ref "D601") (pin "4") (pinfunction "3A_4") (pintype "passive"))
      (node (ref "D601") (pin "7") (pinfunction "3B_7") (pintype "passive"))
      (node (ref "J601") (pin "10") (pinfunction "TRD1-_10") (pintype "passive"))
      (node (ref "U601") (pin "2") (pinfunction "MDI[0]-_2") (pintype "passive"))
    )
    (net (code "17") (name "/MDIO20_P") (class "Default")
      (node (ref "D601") (pin "5") (pinfunction "4A_5") (pintype "passive"))
      (node (ref "D601") (pin "6") (pinfunction "4B_6") (pintype "passive"))
      (node (ref "J601") (pin "11") (pinfunction "TRD1+_11") (pintype "passive"))
      (node (ref "U601") (pin "1") (pinfunction "MDI[0]+_1") (pintype "passive"))
    )
    (net (code "18") (name "/MDIO21_N") (class "Default")
      (node (ref "D601") (pin "1") (pinfunction "1A_1") (pintype "passive"))
      (node (ref "D601") (pin "10") (pinfunction "1B_10") (pintype "passive"))
      (node (ref "J601") (pin "5") (pinfunction "TRD2-_5") (pintype "passive"))
      (node (ref "U601") (pin "5") (pinfunction "MDI[1]-_5") (pintype "passive"))
    )
    (net (code "19") (name "/MDIO21_P") (class "Default")
      (node (ref "D601") (pin "2") (pinfunction "2A_2") (pintype "passive"))
      (node (ref "D601") (pin "9") (pinfunction "2B_9") (pintype "passive"))
      (node (ref "J601") (pin "4") (pinfunction "TRD2+_4") (pintype "passive"))
      (node (ref "U601") (pin "4") (pinfunction "MDI[1]+_4") (pintype "passive"))
    )
    (net (code "20") (name "/MDIO22_N") (class "Default")
      (node (ref "D602") (pin "2") (pinfunction "2A_2") (pintype "passive"))
      (node (ref "D602") (pin "9") (pinfunction "2B_9") (pintype "passive"))
      (node (ref "J601") (pin "2") (pinfunction "TRD3-_2") (pintype "passive"))
      (node (ref "U601") (pin "7") (pinfunction "MDI[2]-_7") (pintype "passive"))
    )
    (net (code "21") (name "/MDIO22_P") (class "Default")
      (node (ref "D602") (pin "1") (pinfunction "1A_1") (pintype "passive"))
      (node (ref "D602") (pin "10") (pinfunction "1B_10") (pintype "passive"))
      (node (ref "J601") (pin "3") (pinfunction "TRD3+_3") (pintype "passive"))
      (node (ref "U601") (pin "6") (pinfunction "MDI[2]+_6") (pintype "passive"))
    )
    (net (code "22") (name "/MDIO23_N") (class "Default")
      (node (ref "D602") (pin "5") (pinfunction "4A_5") (pintype "passive"))
      (node (ref "D602") (pin "6") (pinfunction "4B_6") (pintype "passive"))
      (node (ref "J601") (pin "9") (pinfunction "TRD4-_9") (pintype "passive"))
      (node (ref "U601") (pin "10") (pinfunction "MDI[3]-_10") (pintype "passive"))
    )
    (net (code "23") (name "/MDIO23_P") (class "Default")
      (node (ref "D602") (pin "4") (pinfunction "3A_4") (pintype "passive"))
      (node (ref "D602") (pin "7") (pinfunction "3B_7") (pintype "passive"))
      (node (ref "J601") (pin "8") (pinfunction "TRD4+_8") (pintype "passive"))
      (node (ref "U601") (pin "9") (pinfunction "MDI[3]+_9") (pintype "passive"))
    )
    (net (code "24") (name "/MDIO_2") (class "Default")
      (node (ref "R603") (pin "2") (pinfunction "2_2") (pintype "passive"))
      (node (ref "U601") (pin "14") (pinfunction "MDIO_14") (pintype "passive"))
    )
    (net (code "25") (name "/PHYRSTB_2") (class "Default")
      (node (ref "C613") (pin "2") (pinfunction "2_2") (pintype "passive"))
      (node (ref "Q601") (pin "3") (pinfunction "D_3") (pintype "passive"))
      (node (ref "R625") (pin "1") (pinfunction "1_1") (pintype "passive"))
      (node (ref "U601") (pin "12") (pinfunction "PHYRSTB_12") (pintype "passive"))
    )
    (net (code "26") (name "/PORz_OUT") (class "Default")
      (node (ref "D604") (pin "2") (pinfunction "C_2") (pintype "passive"))
    )
    (net (code "27") (name "/REG_OUT2") (class "Default")
      (node (ref "L601") (pin "1") (pinfunction "1_1") (pintype "passive"))
      (node (ref "U601") (pin "30") (pinfunction "REG_OUT_30") (pintype "power_in"))
    )
    (net (code "28") (name "/RESETSTATz") (class "Default")
      (node (ref "D605") (pin "2") (pinfunction "C_2") (pintype "passive"))
    )
    (net (code "29") (name "/RGMII2_TD0") (class "Default")
      (node (ref "U601") (pin "18") (pinfunction "TXD0_18") (pintype "passive"))
    )
    (net (code "30") (name "/RGMII2_TD1") (class "Default")
      (node (ref "U601") (pin "17") (pinfunction "TXD1_17") (pintype "passive"))
    )
    (net (code "31") (name "/RGMII2_TD2") (class "Default")
      (node (ref "U601") (pin "16") (pinfunction "TXD2_16") (pintype "passive"))
    )
    (net (code "32") (name "/RGMII2_TD4") (class "Default")
      (node (ref "U601") (pin "15") (pinfunction "TXD3_15") (pintype "passive"))
    )
    (net (code "33") (name "/RGMII2_TXC") (class "Default")
      (node (ref "U601") (pin "20") (pinfunction "TXC_20") (pintype "passive"))
    )
    (net (code "34") (name "/RGMII2_TX_CTL") (class "Default")
      (node (ref "U601") (pin "19") (pinfunction "TXCTL_19") (pintype "passive"))
    )
    (net (code "35") (name "/RSET2") (class "Default")
      (node (ref "R605") (pin "1") (pinfunction "1_1") (pintype "passive"))
      (node (ref "U601") (pin "39") (pinfunction "RSET_39") (pintype "passive"))
    )
    (net (code "36") (name "/RXC2{slash}PHYAD1") (class "Default")
      (node (ref "R618") (pin "2") (pinfunction "2_2") (pintype "passive"))
      (node (ref "R619") (pin "1") (pinfunction "1_1") (pintype "passive"))
      (node (ref "U601") (pin "27") (pinfunction "RXC/PHYAD1_27") (pintype "passive"))
    )
    (net (code "37") (name "/RXCTL2{slash}PHYAD2") (class "Default")
      (node (ref "R622") (pin "2") (pinfunction "2_2") (pintype "passive"))
      (node (ref "R623") (pin "1") (pinfunction "1_1") (pintype "passive"))
      (node (ref "U601") (pin "26") (pinfunction "RXCTL/PHYAD2_26") (pintype "passive"))
    )
    (net (code "38") (name "/RXD20{slash}RXDLY") (class "Default")
      (node (ref "R614") (pin "2") (pinfunction "2_2") (pintype "passive"))
      (node (ref "R615") (pin "1") (pinfunction "1_1") (pintype "passive"))
      (node (ref "U601") (pin "25") (pinfunction "RXD0/RXDLY_25") (pintype "passive"))
    )
    (net (code "39") (name "/RXD21{slash}TXDLY") (class "Default")
      (node (ref "R612") (pin "2") (pinfunction "2_2") (pintype "passive"))
      (node (ref "R613") (pin "1") (pinfunction "1_1") (pintype "passive"))
      (node (ref "U601") (pin "24") (pinfunction "RXD1/TXDLY_24") (pintype "passive"))
    )
    (net (code "40") (name "/RXD22{slash}PLLOFF") (class "Default")
      (node (ref "R610") (pin "2") (pinfunction "2_2") (pintype "passive"))
      (node (ref "R611") (pin "1") (pinfunction "1_1") (pintype "passive"))
      (node (ref "U601") (pin "23") (pinfunction "RXD2/PLLOFF_23") (pintype "passive"))
    )
    (net (code "41") (name "/RXD23{slash}PHYAD0") (class "Default")
      (node (ref "R616") (pin "2") (pinfunction "2_2") (pintype "passive"))
      (node (ref "R617") (pin "1") (pinfunction "1_1") (pintype "passive"))
      (node (ref "U601") (pin "22") (pinfunction "RXD3/PHYAD0_22") (pintype "passive"))
    )
    (net (code "42") (name "/TCT2_0") (class "Default")
      (node (ref "C616") (pin "1") (pinfunction "1_1") (pintype "passive"))
      (node (ref "J601") (pin "12") (pinfunction "TRCT1_12") (pintype "passive"))
    )
    (net (code "43") (name "/TCT2_1") (class "Default")
      (node (ref "C617") (pin "1") (pinfunction "1_1") (pintype "passive"))
      (node (ref "J601") (pin "6") (pinfunction "TRCT2_6") (pintype "passive"))
    )
    (net (code "44") (name "/TCT2_2") (class "Default")
      (node (ref "C618") (pin "1") (pinfunction "1_1") (pintype "passive"))
      (node (ref "J601") (pin "1") (pinfunction "TRCT3_1") (pintype "passive"))
    )
    (net (code "45") (name "/TCT2_3") (class "Default")
      (node (ref "C619") (pin "1") (pinfunction "1_1") (pintype "passive"))
      (node (ref "J601") (pin "7") (pinfunction "TRCT4_7") (pintype "passive"))
    )
    (net (code "46") (name "/XTAL_IN_GBE2") (class "Default")
      (node (ref "C621") (pin "1") (pinfunction "1_1") (pintype "passive"))
      (node (ref "U601") (pin "36") (pinfunction "XTAL_IN_36") (pintype "passive"))
      (node (ref "Y601") (pin "1") (pinfunction "1_1") (pintype "passive"))
    )
    (net (code "47") (name "/XTAL_OUT_GBE2") (class "Default")
      (node (ref "C622") (pin "1") (pinfunction "1_1") (pintype "passive"))
      (node (ref "U601") (pin "37") (pinfunction "XTAL_OUT/EXT_CLK_37") (pintype "passive"))
      (node (ref "Y601") (pin "3") (pinfunction "3_3") (pintype "passive"))
    )
    (net (code "48") (name "GND") (class "Default")
      (node (ref "C601") (pin "2") (pinfunction "2_2") (pintype "passive"))
      (node (ref "C602") (pin "2") (pinfunction "2_2") (pintype "passive"))
      (node (ref "C603") (pin "2") (pinfunction "2_2") (pintype "passive"))
      (node (ref "C604") (pin "2") (pinfunction "2_2") (pintype "passive"))
      (node (ref "C605") (pin "2") (pinfunction "2_2") (pintype "passive"))
      (node (ref "C606") (pin "2") (pinfunction "2_2") (pintype "passive"))
      (node (ref "C607") (pin "2") (pinfunction "2_2") (pintype "passive"))
      (node (ref "C608") (pin "2") (pinfunction "2_2") (pintype "passive"))
      (node (ref "C609") (pin "2") (pinfunction "2_2") (pintype "passive"))
      (node (ref "C610") (pin "2") (pinfunction "2_2") (pintype "passive"))
      (node (ref "C611") (pin "2") (pinfunction "2_2") (pintype "passive"))
      (node (ref "C612") (pin "2") (pinfunction "2_2") (pintype "passive"))
      (node (ref "C613") (pin "1") (pinfunction "1_1") (pintype "passive"))
      (node (ref "C614") (pin "1") (pinfunction "1_1") (pintype "passive"))
      (node (ref "C615") (pin "2") (pinfunction "2_2") (pintype "passive"))
      (node (ref "C616") (pin "2") (pinfunction "2_2") (pintype "passive"))
      (node (ref "C617") (pin "2") (pinfunction "2_2") (pintype "passive"))
      (node (ref "C618") (pin "2") (pinfunction "2_2") (pintype "passive"))
      (node (ref "C619") (pin "2") (pinfunction "2_2") (pintype "passive"))
      (node (ref "C620") (pin "2") (pinfunction "2_2") (pintype "passive"))
      (node (ref "C621") (pin "2") (pinfunction "2_2") (pintype "passive"))
      (node (ref "C622") (pin "2") (pinfunction "2_2") (pintype "passive"))
      (node (ref "C623") (pin "1") (pinfunction "1_1") (pintype "passive"))
      (node (ref "D601") (pin "3") (pinfunction "GND1_3") (pintype "passive"))
      (node (ref "D601") (pin "8") (pinfunction "GND1_8") (pintype "passive"))
      (node (ref "D602") (pin "3") (pinfunction "GND1_3") (pintype "passive"))
      (node (ref "D602") (pin "8") (pinfunction "GND1_8") (pintype "passive"))
      (node (ref "R605") (pin "2") (pinfunction "2_2") (pintype "passive"))
      (node (ref "R609") (pin "1") (pinfunction "1_1") (pintype "passive"))
      (node (ref "R610") (pin "1") (pinfunction "1_1") (pintype "passive"))
      (node (ref "R612") (pin "1") (pinfunction "1_1") (pintype "passive"))
      (node (ref "R614") (pin "1") (pinfunction "1_1") (pintype "passive"))
      (node (ref "R616") (pin "1") (pinfunction "1_1") (pintype "passive"))
      (node (ref "R618") (pin "1") (pinfunction "1_1") (pintype "passive"))
      (node (ref "R622") (pin "1") (pinfunction "1_1") (pintype "passive"))
      (node (ref "R626") (pin "1") (pinfunction "1_1") (pintype "passive"))
      (node (ref "R628") (pin "1") (pinfunction "1_1") (pintype "passive"))
      (node (ref "R630") (pin "1") (pinfunction "1_1") (pintype "passive"))
      (node (ref "U601") (pin "41") (pinfunction "EGND_41") (pintype "passive"))
      (node (ref "Y601") (pin "2") (pinfunction "GND_2") (pintype "power_in"))
      (node (ref "Y601") (pin "4") (pinfunction "GND_4") (pintype "power_in"))
    )
    (net (code "49") (name "GND_E") (class "Default")
      (node (ref "C623") (pin "2") (pinfunction "2_2") (pintype "passive"))
      (node (ref "J601") (pin "18") (pinfunction "SHIELD1_18") (pintype "passive"))
      (node (ref "J601") (pin "19") (pinfunction "SHIELD2_19") (pintype "passive"))
      (node (ref "R609") (pin "2") (pinfunction "2_2") (pintype "passive"))
    )
    (net (code "50") (name "Net-(D603-A)") (class "Default")
      (node (ref "D603") (pin "1") (pinfunction "A_1") (pintype "passive"))
      (node (ref "D604") (pin "1") (pinfunction "A_1") (pintype "passive"))
      (node (ref "D605") (pin "1") (pinfunction "A_1") (pintype "passive"))
      (node (ref "Q601") (pin "2") (pinfunction "S_2") (pintype "passive"))
      (node (ref "R624") (pin "1") (pinfunction "1_1") (pintype "passive"))
    )
    (net (code "51") (name "Net-(J601-G_CATODE)") (class "Default")
      (node (ref "J601") (pin "17") (pinfunction "G_CATODE_17") (pintype "passive"))
      (node (ref "R607") (pin "2") (pinfunction "2_2") (pintype "passive"))
    )
    (net (code "52") (name "Net-(J601-O_CATODE)") (class "Default")
      (node (ref "J601") (pin "15") (pinfunction "O_CATODE_15") (pintype "passive"))
      (node (ref "R606") (pin "2") (pinfunction "2_2") (pintype "passive"))
    )
    (net (code "53") (name "Net-(J601-Y_CATODE)") (class "Default")
      (node (ref "J601") (pin "13") (pinfunction "Y_CATODE_13") (pintype "passive"))
      (node (ref "R608") (pin "2") (pinfunction "2_2") (pintype "passive"))
    )
    (net (code "54") (name "PHY2_DVDD3V3") (class "Default")
      (node (ref "C601") (pin "1") (pinfunction "1_1") (pintype "passive"))
      (node (ref "C602") (pin "1") (pinfunction "1_1") (pintype "passive"))
      (node (ref "C620") (pin "1") (pinfunction "1_1") (pintype "passive"))
      (node (ref "FB601") (pin "2") (pinfunction "2_2") (pintype "passive"))
      (node (ref "J601") (pin "14") (pinfunction "Y_ANODE_14") (pintype "passive"))
      (node (ref "J601") (pin "16") (pinfunction "COM_ANODE_16") (pintype "passive"))
      (node (ref "R621") (pin "2") (pinfunction "2_2") (pintype "passive"))
      (node (ref "R625") (pin "2") (pinfunction "2_2") (pintype "passive"))
      (node (ref "R627") (pin "2") (pinfunction "2_2") (pintype "passive"))
      (node (ref "R629") (pin "2") (pinfunction "2_2") (pintype "passive"))
      (node (ref "R631") (pin "2") (pinfunction "2_2") (pintype "passive"))
      (node (ref "U601") (pin "29") (pinfunction "DVDD33_29_29") (pintype "power_in"))
    )
    (net (code "55") (name "PHY2_VDD1V0") (class "Default")
      (node (ref "C614") (pin "2") (pinfunction "2_2") (pintype "passive"))
      (node (ref "C615") (pin "1") (pinfunction "1_1") (pintype "passive"))
      (node (ref "FB602") (pin "2") (pinfunction "2_2") (pintype "passive"))
      (node (ref "FB603") (pin "1") (pinfunction "1_1") (pintype "passive"))
      (node (ref "L601") (pin "2") (pinfunction "2_2") (pintype "passive"))
    )
    (net (code "56") (name "PHY2_VDDIO") (class "Default")
      (node (ref "C605") (pin "1") (pinfunction "1_1") (pintype "passive"))
      (node (ref "C606") (pin "1") (pinfunction "1_1") (pintype "passive"))
      (node (ref "R601") (pin "1") (pinfunction "1_1") (pintype "passive"))
      (node (ref "R611") (pin "2") (pinfunction "2_2") (pintype "passive"))
      (node (ref "R613") (pin "2") (pinfunction "2_2") (pintype "passive"))
      (node (ref "R615") (pin "2") (pinfunction "2_2") (pintype "passive"))
      (node (ref "R617") (pin "2") (pinfunction "2_2") (pintype "passive"))
      (node (ref "R619") (pin "2") (pinfunction "2_2") (pintype "passive"))
      (node (ref "R623") (pin "2") (pinfunction "2_2") (pintype "passive"))
      (node (ref "U601") (pin "28") (pinfunction "DVDD_RG_28") (pintype "power_in"))
    )
  )
)
